# CL-KB-V1_2.net
KiCad netlist of a schematic drawn in Altium Designer
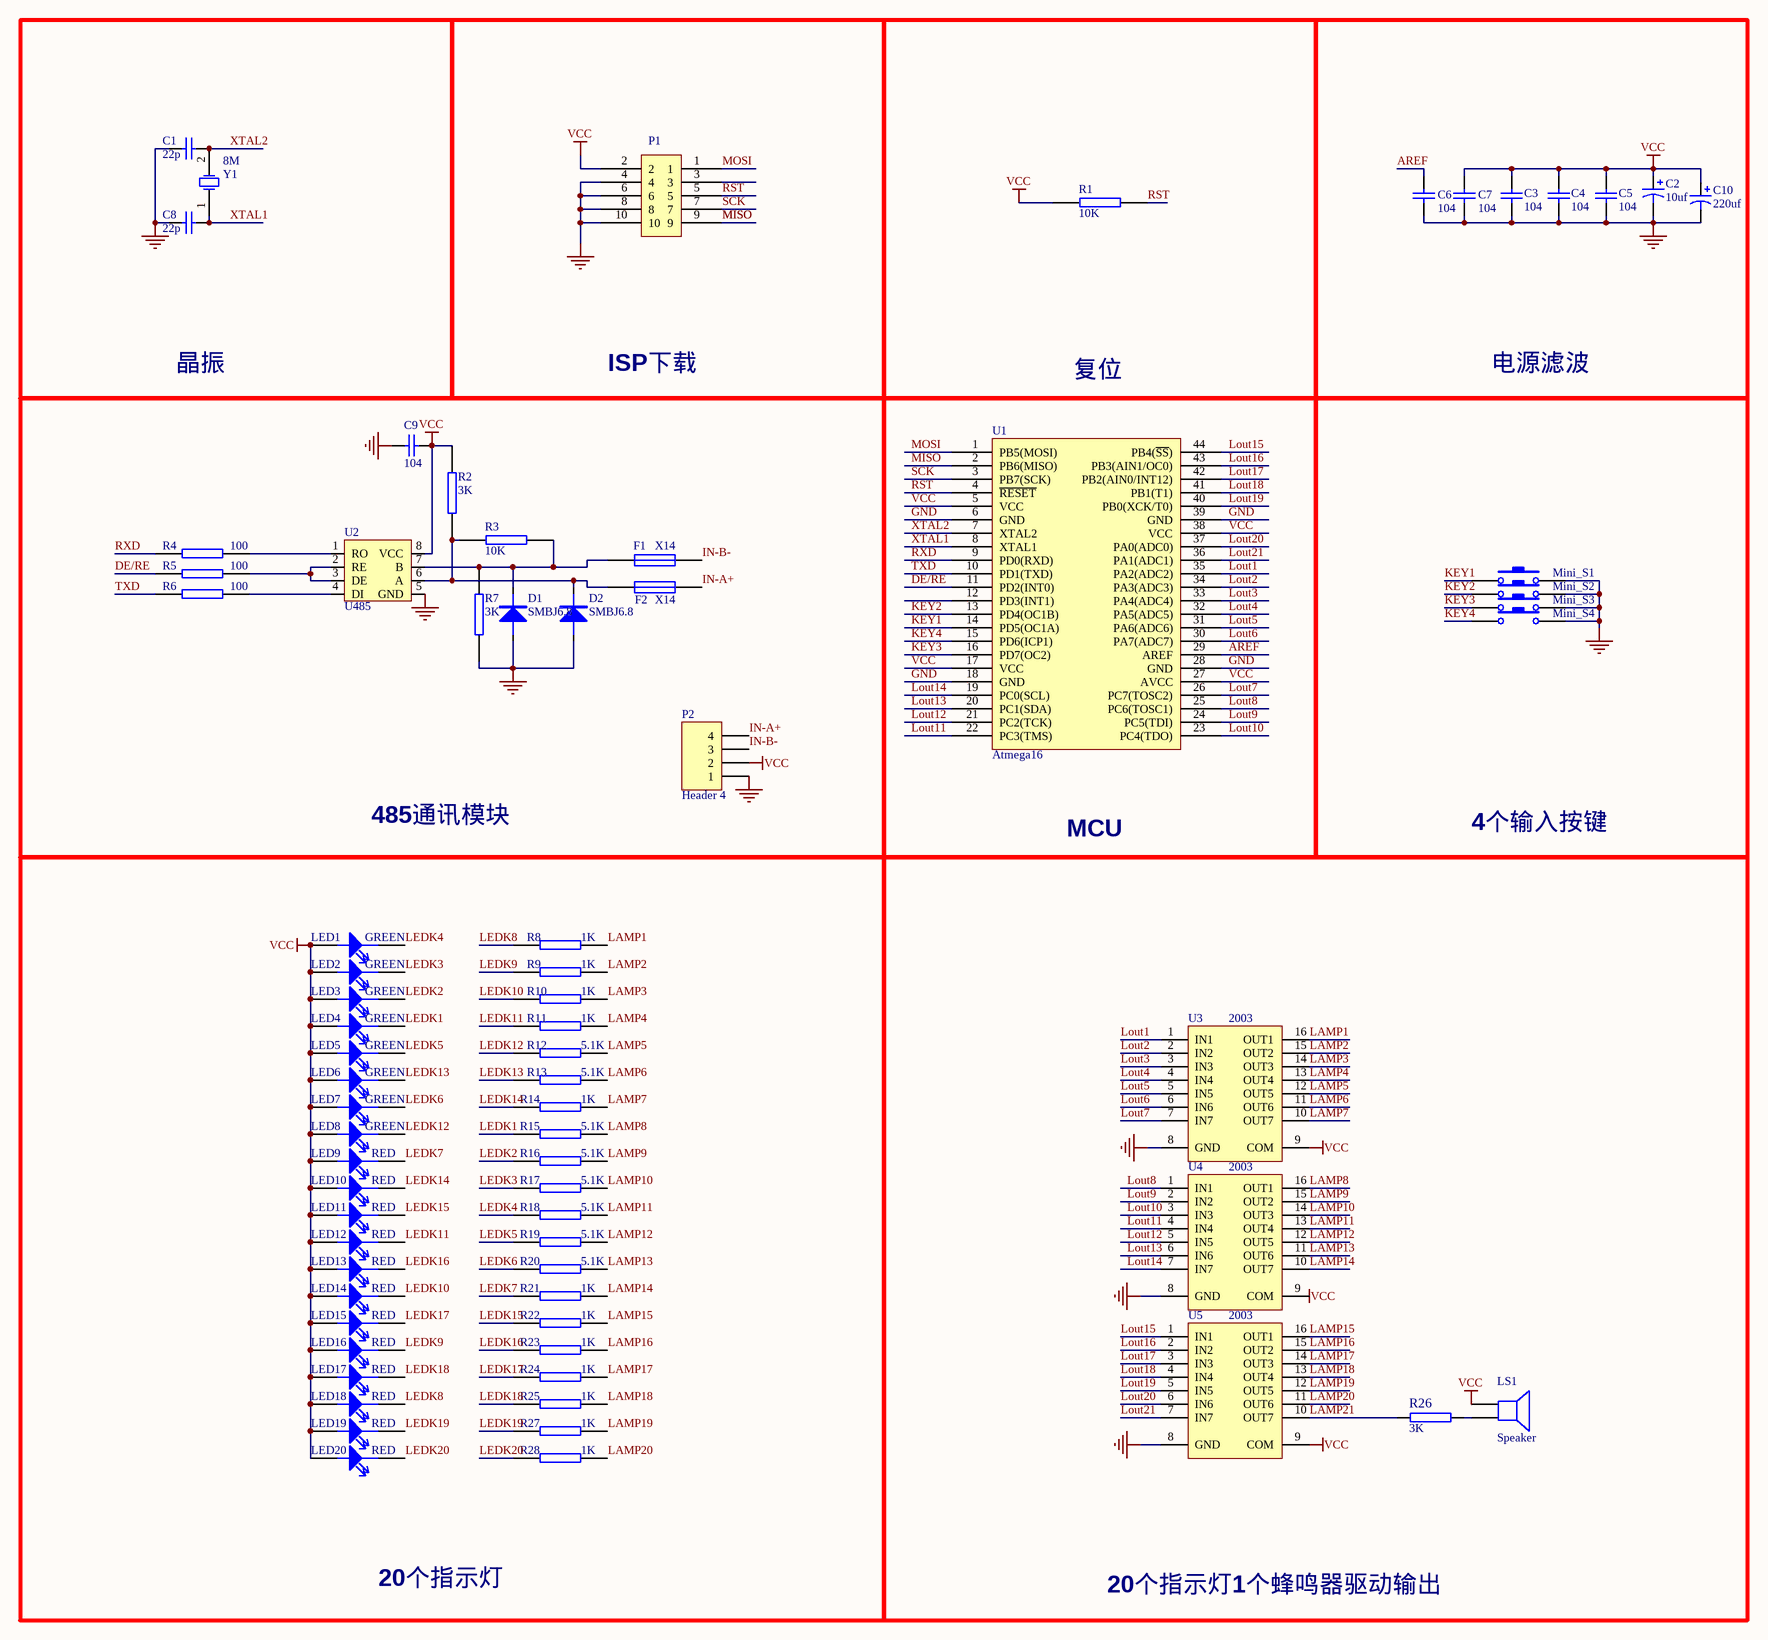
[diagram p0: CL-KB-V1.2.SchDoc]

(export (version "E")
  (design (tool "Eeschema 10.0.6"))
  (components
    (comp (ref "C1")
      (value "22p")
      (footprint "c0805c")
      (description "Capacitor")
      (fields (field (name "PUBLISHER") "Altium Limited"))
      (libsource (lib "*") (part "Cap"))
    )
    (comp (ref "C2")
      (value "10uf")
      (footprint "E6.5MM")
      (description "Polarized Capacitor (Radial)")
      (fields (field (name "PUBLISHER") "Altium Limited"))
      (libsource (lib "PCB_Project1") (part "Cap Pol1"))
    )
    (comp (ref "C3")
      (value "104")
      (footprint "c0805c")
      (description "Capacitor")
      (fields (field (name "PUBLISHER") "Altium Limited"))
      (libsource (lib "*") (part "Cap"))
    )
    (comp (ref "C4")
      (value "104")
      (footprint "c0805c")
      (description "Capacitor")
      (fields (field (name "PUBLISHER") "Altium Limited"))
      (libsource (lib "*") (part "Cap"))
    )
    (comp (ref "C5")
      (value "104")
      (footprint "c0805c")
      (description "Capacitor")
      (fields (field (name "PUBLISHER") "Altium Limited"))
      (libsource (lib "*") (part "Cap"))
    )
    (comp (ref "C6")
      (value "104")
      (footprint "c0805c")
      (description "Capacitor")
      (fields (field (name "PUBLISHER") "Altium Limited"))
      (libsource (lib "*") (part "Cap"))
    )
    (comp (ref "C7")
      (value "104")
      (footprint "c0805c")
      (description "Capacitor")
      (fields (field (name "PUBLISHER") "Altium Limited"))
      (libsource (lib "*") (part "Cap"))
    )
    (comp (ref "C8")
      (value "22p")
      (footprint "c0805c")
      (description "Capacitor")
      (fields (field (name "PUBLISHER") "Altium Limited"))
      (libsource (lib "*") (part "Cap"))
    )
    (comp (ref "C9")
      (value "104")
      (footprint "c0805c")
      (description "Capacitor")
      (fields (field (name "PUBLISHER") "Altium Limited"))
      (libsource (lib "*") (part "Cap"))
    )
    (comp (ref "C10")
      (value "220uf")
      (footprint "E6.5MM")
      (description "Polarized Capacitor (Radial)")
      (fields (field (name "PUBLISHER") "Altium Limited"))
      (libsource (lib "PCB_Project1") (part "Cap Pol1"))
    )
    (comp (ref "D1")
      (value "SMBJ6.8")
      (footprint "SMBJ_SMT")
      (description "Diode")
      (libsource (lib "*") (part "DIODE"))
    )
    (comp (ref "D2")
      (value "SMBJ6.8")
      (footprint "SMBJ_SMT")
      (description "Diode")
      (libsource (lib "*") (part "DIODE"))
    )
    (comp (ref "F1")
      (value "X14")
      (footprint "PPTC_SMT")
      (description "Fuse")
      (fields (field (name "PUBLISHER") "Altium Limited"))
      (libsource (lib "Miscellaneous Devices") (part "Fuse 1"))
    )
    (comp (ref "F2")
      (value "X14")
      (footprint "PPTC_SMT")
      (description "Fuse")
      (fields (field (name "PUBLISHER") "Altium Limited"))
      (libsource (lib "Miscellaneous Devices") (part "Fuse 1"))
    )
    (comp (ref "LED1")
      (value "GREEN")
      (footprint "PLED10*10")
      (description "Zener Diode")
      (libsource (lib "*") (part "LED"))
    )
    (comp (ref "LED2")
      (value "GREEN")
      (footprint "PLED10*10")
      (description "Zener Diode")
      (libsource (lib "*") (part "LED"))
    )
    (comp (ref "LED3")
      (value "GREEN")
      (footprint "PLED10*10")
      (description "Zener Diode")
      (libsource (lib "*") (part "LED"))
    )
    (comp (ref "LED4")
      (value "GREEN")
      (footprint "PLED10*10")
      (description "Zener Diode")
      (libsource (lib "*") (part "LED"))
    )
    (comp (ref "LED5")
      (value "GREEN")
      (footprint "PLED10*10")
      (description "Zener Diode")
      (libsource (lib "*") (part "LED"))
    )
    (comp (ref "LED6")
      (value "GREEN")
      (footprint "PLED10*10")
      (description "Zener Diode")
      (libsource (lib "*") (part "LED"))
    )
    (comp (ref "LED7")
      (value "GREEN")
      (footprint "PLED10*10")
      (description "Zener Diode")
      (libsource (lib "*") (part "LED"))
    )
    (comp (ref "LED8")
      (value "GREEN")
      (footprint "PLED10*10")
      (description "Zener Diode")
      (libsource (lib "*") (part "LED"))
    )
    (comp (ref "LED9")
      (value "RED")
      (footprint "PLED10*10")
      (description "Zener Diode")
      (libsource (lib "*") (part "LED"))
    )
    (comp (ref "LED10")
      (value "RED")
      (footprint "PLED10*10")
      (description "Zener Diode")
      (libsource (lib "*") (part "LED"))
    )
    (comp (ref "LED11")
      (value "RED")
      (footprint "PLED10*10")
      (description "Zener Diode")
      (libsource (lib "*") (part "LED"))
    )
    (comp (ref "LED12")
      (value "RED")
      (footprint "PLED10*10")
      (description "Zener Diode")
      (libsource (lib "*") (part "LED"))
    )
    (comp (ref "LED13")
      (value "RED")
      (footprint "PLED10*10")
      (description "Zener Diode")
      (libsource (lib "*") (part "LED"))
    )
    (comp (ref "LED14")
      (value "RED")
      (footprint "PLED10*10")
      (description "Zener Diode")
      (libsource (lib "*") (part "LED"))
    )
    (comp (ref "LED15")
      (value "RED")
      (footprint "PLED10*10")
      (description "Zener Diode")
      (libsource (lib "*") (part "LED"))
    )
    (comp (ref "LED16")
      (value "RED")
      (footprint "PLED10*10")
      (description "Zener Diode")
      (libsource (lib "*") (part "LED"))
    )
    (comp (ref "LED17")
      (value "RED")
      (footprint "PLED10*10")
      (description "Zener Diode")
      (libsource (lib "*") (part "LED"))
    )
    (comp (ref "LED18")
      (value "RED")
      (footprint "PLED10*10")
      (description "Zener Diode")
      (libsource (lib "*") (part "LED"))
    )
    (comp (ref "LED19")
      (value "RED")
      (footprint "PLED10*10")
      (description "Zener Diode")
      (libsource (lib "*") (part "LED"))
    )
    (comp (ref "LED20")
      (value "RED")
      (footprint "PLED10*10")
      (description "Zener Diode")
      (libsource (lib "*") (part "LED"))
    )
    (comp (ref "LS1")
      (value "Speaker")
      (footprint "SPK")
      (description "Loudspeaker")
      (fields (field (name "PUBLISHER") "Altium Limited"))
      (libsource (lib "Miscellaneous Devices") (part "Speaker"))
    )
    (comp (ref "Mini_S1")
      (value "~")
      (footprint "KEYL")
      (description "Switch")
      (fields (field (name "PUBLISHER") "Altium Limited"))
      (libsource (lib "Miscellaneous Devices") (part "SW-PB"))
    )
    (comp (ref "Mini_S2")
      (value "~")
      (footprint "KEYL")
      (description "Switch")
      (fields (field (name "PUBLISHER") "Altium Limited"))
      (libsource (lib "Miscellaneous Devices") (part "SW-PB"))
    )
    (comp (ref "Mini_S3")
      (value "~")
      (footprint "KEYL")
      (description "Switch")
      (fields (field (name "PUBLISHER") "Altium Limited"))
      (libsource (lib "Miscellaneous Devices") (part "SW-PB"))
    )
    (comp (ref "Mini_S4")
      (value "~")
      (footprint "KEYL")
      (description "Switch")
      (fields (field (name "PUBLISHER") "Altium Limited"))
      (libsource (lib "Miscellaneous Devices") (part "SW-PB"))
    )
    (comp (ref "P1") (value "CON10") (footprint "ISP") (libsource (lib "能迪SCH库") (part "SPI10")))
    (comp (ref "P2")
      (value "Header 4")
      (footprint "C3-4L")
      (description "Header, 4-Pin")
      (fields (field (name "PUBLISHER") "Altium Limited"))
      (libsource (lib "Miscellaneous Connectors") (part "Header 4"))
    )
    (comp (ref "R1") (value "10K") (footprint "0805C") (libsource (lib "") (part "RES2_1")))
    (comp (ref "R2") (value "3K") (footprint "0805C") (libsource (lib "") (part "RES2_1")))
    (comp (ref "R3") (value "10K") (footprint "0805C") (libsource (lib "") (part "RES2_1")))
    (comp (ref "R4") (value "100") (footprint "0805C") (libsource (lib "*") (part "RES2")))
    (comp (ref "R5") (value "100") (footprint "0805C") (libsource (lib "*") (part "RES2")))
    (comp (ref "R6") (value "100") (footprint "0805C") (libsource (lib "*") (part "RES2")))
    (comp (ref "R7") (value "3K") (footprint "0805C") (libsource (lib "") (part "RES2_1")))
    (comp (ref "R8") (value "1K") (footprint "0805C") (libsource (lib "") (part "RES2_1")))
    (comp (ref "R9") (value "1K") (footprint "0805C") (libsource (lib "") (part "RES2_1")))
    (comp (ref "R10") (value "1K") (footprint "0805C") (libsource (lib "") (part "RES2_1")))
    (comp (ref "R11") (value "1K") (footprint "0805C") (libsource (lib "") (part "RES2_1")))
    (comp (ref "R12") (value "5.1K") (footprint "0805C") (libsource (lib "") (part "RES2_1")))
    (comp (ref "R13") (value "5.1K") (footprint "0805C") (libsource (lib "") (part "RES2_1")))
    (comp (ref "R14") (value "1K") (footprint "0805C") (libsource (lib "") (part "RES2_1")))
    (comp (ref "R15") (value "5.1K") (footprint "0805C") (libsource (lib "") (part "RES2_1")))
    (comp (ref "R16") (value "5.1K") (footprint "0805C") (libsource (lib "") (part "RES2_1")))
    (comp (ref "R17") (value "5.1K") (footprint "0805C") (libsource (lib "") (part "RES2_1")))
    (comp (ref "R18") (value "5.1K") (footprint "0805C") (libsource (lib "") (part "RES2_1")))
    (comp (ref "R19") (value "5.1K") (footprint "0805C") (libsource (lib "") (part "RES2_1")))
    (comp (ref "R20") (value "5.1K") (footprint "0805C") (libsource (lib "") (part "RES2_1")))
    (comp (ref "R21") (value "1K") (footprint "0805C") (libsource (lib "") (part "RES2_1")))
    (comp (ref "R22") (value "1K") (footprint "0805C") (libsource (lib "") (part "RES2_1")))
    (comp (ref "R23") (value "1K") (footprint "0805C") (libsource (lib "") (part "RES2_1")))
    (comp (ref "R24") (value "1K") (footprint "0805C") (libsource (lib "") (part "RES2_1")))
    (comp (ref "R25") (value "1K") (footprint "0805C") (libsource (lib "") (part "RES2_1")))
    (comp (ref "R26") (value "3K") (footprint "0805C") (libsource (lib "") (part "RES2_2")))
    (comp (ref "R27") (value "1K") (footprint "0805C") (libsource (lib "") (part "RES2_1")))
    (comp (ref "R28") (value "1K") (footprint "0805C") (libsource (lib "") (part "RES2_1")))
    (comp (ref "U1")
      (value "Atmega16")
      (footprint "QFP44")
      (libsource (lib "CL_FS_A(V1.0)") (part "Atmega16"))
    )
    (comp (ref "U2") (value "U485") (footprint "SOP8") (libsource (lib "POL485") (part "U485")))
    (comp (ref "U3")
      (value "2003")
      (footprint "SO_16")
      (description "High-Voltage, High-Current Darlington Array")
      (fields (field (name "PUBLISHER") "*"))
      (libsource (lib "*") (part "ULN2003A"))
    )
    (comp (ref "U4")
      (value "2003")
      (footprint "SO_16")
      (description "High-Voltage, High-Current Darlington Array")
      (fields (field (name "PUBLISHER") "*"))
      (libsource (lib "*") (part "ULN2003A"))
    )
    (comp (ref "U5")
      (value "2003")
      (footprint "SO_16")
      (description "High-Voltage, High-Current Darlington Array")
      (fields (field (name "PUBLISHER") "*"))
      (libsource (lib "*") (part "ULN2003A"))
    )
    (comp (ref "Y1")
      (value "8M")
      (footprint "XTP2")
      (description "Crystal Oscillator")
      (fields (field (name "PUBLISHER") "Altium Limited"))
      (libsource (lib "*") (part "XTAL"))
    )
  )
  (nets
    (net (code "1") (name "/AREF") (class "Default")
      (node (ref "C6") (pin "2") (pinfunction "2_2") (pintype "passive"))
      (node (ref "U1") (pin "29") (pinfunction "AREF_29") (pintype "passive"))
    )
    (net (code "2") (name "/DE{slash}RE") (class "Default")
      (node (ref "R5") (pin "2") (pinfunction "2_2") (pintype "passive"))
      (node (ref "U1") (pin "11") (pinfunction "PD2(INT0)_11") (pintype "passive"))
    )
    (net (code "3") (name "/IN-A+") (class "Default")
      (node (ref "F2") (pin "1") (pinfunction "1_1") (pintype "passive"))
      (node (ref "P2") (pin "4") (pinfunction "4_4") (pintype "passive"))
    )
    (net (code "4") (name "/IN-B-") (class "Default")
      (node (ref "F1") (pin "1") (pinfunction "1_1") (pintype "passive"))
      (node (ref "P2") (pin "3") (pinfunction "3_3") (pintype "passive"))
    )
    (net (code "5") (name "/KEY1") (class "Default")
      (node (ref "Mini_S1") (pin "1") (pinfunction "1_1") (pintype "passive"))
      (node (ref "U1") (pin "14") (pinfunction "PD5(OC1A)_14") (pintype "passive"))
    )
    (net (code "6") (name "/KEY2") (class "Default")
      (node (ref "Mini_S2") (pin "1") (pinfunction "1_1") (pintype "passive"))
      (node (ref "U1") (pin "13") (pinfunction "PD4(OC1B)_13") (pintype "passive"))
    )
    (net (code "7") (name "/KEY3") (class "Default")
      (node (ref "Mini_S3") (pin "1") (pinfunction "1_1") (pintype "passive"))
      (node (ref "U1") (pin "16") (pinfunction "PD7(OC2)_16") (pintype "passive"))
    )
    (net (code "8") (name "/KEY4") (class "Default")
      (node (ref "Mini_S4") (pin "1") (pinfunction "1_1") (pintype "passive"))
      (node (ref "U1") (pin "15") (pinfunction "PD6(ICP1)_15") (pintype "passive"))
    )
    (net (code "9") (name "/LAMP1") (class "Default")
      (node (ref "R8") (pin "2") (pinfunction "2_2") (pintype "passive"))
      (node (ref "U3") (pin "16") (pinfunction "OUT1_16") (pintype "open_collector"))
    )
    (net (code "10") (name "/LAMP2") (class "Default")
      (node (ref "R9") (pin "2") (pinfunction "2_2") (pintype "passive"))
      (node (ref "U3") (pin "15") (pinfunction "OUT2_15") (pintype "open_collector"))
    )
    (net (code "11") (name "/LAMP3") (class "Default")
      (node (ref "R10") (pin "2") (pinfunction "2_2") (pintype "passive"))
      (node (ref "U3") (pin "14") (pinfunction "OUT3_14") (pintype "open_collector"))
    )
    (net (code "12") (name "/LAMP4") (class "Default")
      (node (ref "R11") (pin "2") (pinfunction "2_2") (pintype "passive"))
      (node (ref "U3") (pin "13") (pinfunction "OUT4_13") (pintype "open_collector"))
    )
    (net (code "13") (name "/LAMP5") (class "Default")
      (node (ref "R12") (pin "2") (pinfunction "2_2") (pintype "passive"))
      (node (ref "U3") (pin "12") (pinfunction "OUT5_12") (pintype "open_collector"))
    )
    (net (code "14") (name "/LAMP6") (class "Default")
      (node (ref "R13") (pin "2") (pinfunction "2_2") (pintype "passive"))
      (node (ref "U3") (pin "11") (pinfunction "OUT6_11") (pintype "open_collector"))
    )
    (net (code "15") (name "/LAMP7") (class "Default")
      (node (ref "R14") (pin "2") (pinfunction "2_2") (pintype "passive"))
      (node (ref "U3") (pin "10") (pinfunction "OUT7_10") (pintype "open_collector"))
    )
    (net (code "16") (name "/LAMP8") (class "Default")
      (node (ref "R15") (pin "2") (pinfunction "2_2") (pintype "passive"))
      (node (ref "U4") (pin "16") (pinfunction "OUT1_16") (pintype "open_collector"))
    )
    (net (code "17") (name "/LAMP9") (class "Default")
      (node (ref "R16") (pin "2") (pinfunction "2_2") (pintype "passive"))
      (node (ref "U4") (pin "15") (pinfunction "OUT2_15") (pintype "open_collector"))
    )
    (net (code "18") (name "/LAMP10") (class "Default")
      (node (ref "R17") (pin "2") (pinfunction "2_2") (pintype "passive"))
      (node (ref "U4") (pin "14") (pinfunction "OUT3_14") (pintype "open_collector"))
    )
    (net (code "19") (name "/LAMP11") (class "Default")
      (node (ref "R18") (pin "2") (pinfunction "2_2") (pintype "passive"))
      (node (ref "U4") (pin "13") (pinfunction "OUT4_13") (pintype "open_collector"))
    )
    (net (code "20") (name "/LAMP12") (class "Default")
      (node (ref "R19") (pin "2") (pinfunction "2_2") (pintype "passive"))
      (node (ref "U4") (pin "12") (pinfunction "OUT5_12") (pintype "open_collector"))
    )
    (net (code "21") (name "/LAMP13") (class "Default")
      (node (ref "R20") (pin "2") (pinfunction "2_2") (pintype "passive"))
      (node (ref "U4") (pin "11") (pinfunction "OUT6_11") (pintype "open_collector"))
    )
    (net (code "22") (name "/LAMP14") (class "Default")
      (node (ref "R21") (pin "2") (pinfunction "2_2") (pintype "passive"))
      (node (ref "U4") (pin "10") (pinfunction "OUT7_10") (pintype "open_collector"))
    )
    (net (code "23") (name "/LAMP15") (class "Default")
      (node (ref "R22") (pin "2") (pinfunction "2_2") (pintype "passive"))
      (node (ref "U5") (pin "16") (pinfunction "OUT1_16") (pintype "open_collector"))
    )
    (net (code "24") (name "/LAMP16") (class "Default")
      (node (ref "R23") (pin "2") (pinfunction "2_2") (pintype "passive"))
      (node (ref "U5") (pin "15") (pinfunction "OUT2_15") (pintype "open_collector"))
    )
    (net (code "25") (name "/LAMP17") (class "Default")
      (node (ref "R24") (pin "2") (pinfunction "2_2") (pintype "passive"))
      (node (ref "U5") (pin "14") (pinfunction "OUT3_14") (pintype "open_collector"))
    )
    (net (code "26") (name "/LAMP18") (class "Default")
      (node (ref "R25") (pin "2") (pinfunction "2_2") (pintype "passive"))
      (node (ref "U5") (pin "13") (pinfunction "OUT4_13") (pintype "open_collector"))
    )
    (net (code "27") (name "/LAMP19") (class "Default")
      (node (ref "R27") (pin "2") (pinfunction "2_2") (pintype "passive"))
      (node (ref "U5") (pin "12") (pinfunction "OUT5_12") (pintype "open_collector"))
    )
    (net (code "28") (name "/LAMP20") (class "Default")
      (node (ref "R28") (pin "2") (pinfunction "2_2") (pintype "passive"))
      (node (ref "U5") (pin "11") (pinfunction "OUT6_11") (pintype "open_collector"))
    )
    (net (code "29") (name "/LAMP21") (class "Default")
      (node (ref "R26") (pin "1") (pintype "passive"))
      (node (ref "U5") (pin "10") (pinfunction "OUT7_10") (pintype "open_collector"))
    )
    (net (code "30") (name "/LEDK1") (class "Default")
      (node (ref "LED4") (pin "K") (pinfunction "K_K") (pintype "passive"))
      (node (ref "R15") (pin "1") (pinfunction "1_1") (pintype "passive"))
    )
    (net (code "31") (name "/LEDK2") (class "Default")
      (node (ref "LED3") (pin "K") (pinfunction "K_K") (pintype "passive"))
      (node (ref "R16") (pin "1") (pinfunction "1_1") (pintype "passive"))
    )
    (net (code "32") (name "/LEDK3") (class "Default")
      (node (ref "LED2") (pin "K") (pinfunction "K_K") (pintype "passive"))
      (node (ref "R17") (pin "1") (pinfunction "1_1") (pintype "passive"))
    )
    (net (code "33") (name "/LEDK4") (class "Default")
      (node (ref "LED1") (pin "K") (pinfunction "K_K") (pintype "passive"))
      (node (ref "R18") (pin "1") (pinfunction "1_1") (pintype "passive"))
    )
    (net (code "34") (name "/LEDK5") (class "Default")
      (node (ref "LED5") (pin "K") (pinfunction "K_K") (pintype "passive"))
      (node (ref "R19") (pin "1") (pinfunction "1_1") (pintype "passive"))
    )
    (net (code "35") (name "/LEDK6") (class "Default")
      (node (ref "LED7") (pin "K") (pinfunction "K_K") (pintype "passive"))
      (node (ref "R20") (pin "1") (pinfunction "1_1") (pintype "passive"))
    )
    (net (code "36") (name "/LEDK7") (class "Default")
      (node (ref "LED9") (pin "K") (pinfunction "K_K") (pintype "passive"))
      (node (ref "R21") (pin "1") (pinfunction "1_1") (pintype "passive"))
    )
    (net (code "37") (name "/LEDK8") (class "Default")
      (node (ref "LED18") (pin "K") (pinfunction "K_K") (pintype "passive"))
      (node (ref "R8") (pin "1") (pinfunction "1_1") (pintype "passive"))
    )
    (net (code "38") (name "/LEDK9") (class "Default")
      (node (ref "LED16") (pin "K") (pinfunction "K_K") (pintype "passive"))
      (node (ref "R9") (pin "1") (pinfunction "1_1") (pintype "passive"))
    )
    (net (code "39") (name "/LEDK10") (class "Default")
      (node (ref "LED14") (pin "K") (pinfunction "K_K") (pintype "passive"))
      (node (ref "R10") (pin "1") (pinfunction "1_1") (pintype "passive"))
    )
    (net (code "40") (name "/LEDK11") (class "Default")
      (node (ref "LED12") (pin "K") (pinfunction "K_K") (pintype "passive"))
      (node (ref "R11") (pin "1") (pinfunction "1_1") (pintype "passive"))
    )
    (net (code "41") (name "/LEDK12") (class "Default")
      (node (ref "LED8") (pin "K") (pinfunction "K_K") (pintype "passive"))
      (node (ref "R12") (pin "1") (pinfunction "1_1") (pintype "passive"))
    )
    (net (code "42") (name "/LEDK13") (class "Default")
      (node (ref "LED6") (pin "K") (pinfunction "K_K") (pintype "passive"))
      (node (ref "R13") (pin "1") (pinfunction "1_1") (pintype "passive"))
    )
    (net (code "43") (name "/LEDK14") (class "Default")
      (node (ref "LED10") (pin "K") (pinfunction "K_K") (pintype "passive"))
      (node (ref "R14") (pin "1") (pinfunction "1_1") (pintype "passive"))
    )
    (net (code "44") (name "/LEDK15") (class "Default")
      (node (ref "LED11") (pin "K") (pinfunction "K_K") (pintype "passive"))
      (node (ref "R22") (pin "1") (pinfunction "1_1") (pintype "passive"))
    )
    (net (code "45") (name "/LEDK16") (class "Default")
      (node (ref "LED13") (pin "K") (pinfunction "K_K") (pintype "passive"))
      (node (ref "R23") (pin "1") (pinfunction "1_1") (pintype "passive"))
    )
    (net (code "46") (name "/LEDK17") (class "Default")
      (node (ref "LED15") (pin "K") (pinfunction "K_K") (pintype "passive"))
      (node (ref "R24") (pin "1") (pinfunction "1_1") (pintype "passive"))
    )
    (net (code "47") (name "/LEDK18") (class "Default")
      (node (ref "LED17") (pin "K") (pinfunction "K_K") (pintype "passive"))
      (node (ref "R25") (pin "1") (pinfunction "1_1") (pintype "passive"))
    )
    (net (code "48") (name "/LEDK19") (class "Default")
      (node (ref "LED19") (pin "K") (pinfunction "K_K") (pintype "passive"))
      (node (ref "R27") (pin "1") (pinfunction "1_1") (pintype "passive"))
    )
    (net (code "49") (name "/LEDK20") (class "Default")
      (node (ref "LED20") (pin "K") (pinfunction "K_K") (pintype "passive"))
      (node (ref "R28") (pin "1") (pinfunction "1_1") (pintype "passive"))
    )
    (net (code "50") (name "/Lout1") (class "Default")
      (node (ref "U1") (pin "35") (pinfunction "PA2(ADC2)_35") (pintype "passive"))
      (node (ref "U3") (pin "1") (pinfunction "IN1_1") (pintype "passive"))
    )
    (net (code "51") (name "/Lout2") (class "Default")
      (node (ref "U1") (pin "34") (pinfunction "PA3(ADC3)_34") (pintype "passive"))
      (node (ref "U3") (pin "2") (pinfunction "IN2_2") (pintype "passive"))
    )
    (net (code "52") (name "/Lout3") (class "Default")
      (node (ref "U1") (pin "33") (pinfunction "PA4(ADC4)_33") (pintype "passive"))
      (node (ref "U3") (pin "3") (pinfunction "IN3_3") (pintype "passive"))
    )
    (net (code "53") (name "/Lout4") (class "Default")
      (node (ref "U1") (pin "32") (pinfunction "PA5(ADC5)_32") (pintype "passive"))
      (node (ref "U3") (pin "4") (pinfunction "IN4_4") (pintype "passive"))
    )
    (net (code "54") (name "/Lout5") (class "Default")
      (node (ref "U1") (pin "31") (pinfunction "PA6(ADC6)_31") (pintype "passive"))
      (node (ref "U3") (pin "5") (pinfunction "IN5_5") (pintype "passive"))
    )
    (net (code "55") (name "/Lout6") (class "Default")
      (node (ref "U1") (pin "30") (pinfunction "PA7(ADC7)_30") (pintype "passive"))
      (node (ref "U3") (pin "6") (pinfunction "IN6_6") (pintype "passive"))
    )
    (net (code "56") (name "/Lout7") (class "Default")
      (node (ref "U1") (pin "26") (pinfunction "PC7(TOSC2)_26") (pintype "passive"))
      (node (ref "U3") (pin "7") (pinfunction "IN7_7") (pintype "passive"))
    )
    (net (code "57") (name "/Lout8") (class "Default")
      (node (ref "U1") (pin "25") (pinfunction "PC6(TOSC1)_25") (pintype "passive"))
      (node (ref "U4") (pin "1") (pinfunction "IN1_1") (pintype "passive"))
    )
    (net (code "58") (name "/Lout9") (class "Default")
      (node (ref "U1") (pin "24") (pinfunction "PC5(TDI)_24") (pintype "passive"))
      (node (ref "U4") (pin "2") (pinfunction "IN2_2") (pintype "passive"))
    )
    (net (code "59") (name "/Lout10") (class "Default")
      (node (ref "U1") (pin "23") (pinfunction "PC4(TDO)_23") (pintype "passive"))
      (node (ref "U4") (pin "3") (pinfunction "IN3_3") (pintype "passive"))
    )
    (net (code "60") (name "/Lout11") (class "Default")
      (node (ref "U1") (pin "22") (pinfunction "PC3(TMS)_22") (pintype "passive"))
      (node (ref "U4") (pin "4") (pinfunction "IN4_4") (pintype "passive"))
    )
    (net (code "61") (name "/Lout12") (class "Default")
      (node (ref "U1") (pin "21") (pinfunction "PC2(TCK)_21") (pintype "passive"))
      (node (ref "U4") (pin "5") (pinfunction "IN5_5") (pintype "passive"))
    )
    (net (code "62") (name "/Lout13") (class "Default")
      (node (ref "U1") (pin "20") (pinfunction "PC1(SDA)_20") (pintype "passive"))
      (node (ref "U4") (pin "6") (pinfunction "IN6_6") (pintype "passive"))
    )
    (net (code "63") (name "/Lout14") (class "Default")
      (node (ref "U1") (pin "19") (pinfunction "PC0(SCL)_19") (pintype "passive"))
      (node (ref "U4") (pin "7") (pinfunction "IN7_7") (pintype "passive"))
    )
    (net (code "64") (name "/Lout15") (class "Default")
      (node (ref "U1") (pin "44") (pinfunction "PB4(~{SS})_44") (pintype "passive"))
      (node (ref "U5") (pin "1") (pinfunction "IN1_1") (pintype "passive"))
    )
    (net (code "65") (name "/Lout16") (class "Default")
      (node (ref "U1") (pin "43") (pinfunction "PB3(AIN1/OC0)_43") (pintype "passive"))
      (node (ref "U5") (pin "2") (pinfunction "IN2_2") (pintype "passive"))
    )
    (net (code "66") (name "/Lout17") (class "Default")
      (node (ref "U1") (pin "42") (pinfunction "PB2(AIN0/INT12)_42") (pintype "passive"))
      (node (ref "U5") (pin "3") (pinfunction "IN3_3") (pintype "passive"))
    )
    (net (code "67") (name "/Lout18") (class "Default")
      (node (ref "U1") (pin "41") (pinfunction "PB1(T1)_41") (pintype "passive"))
      (node (ref "U5") (pin "4") (pinfunction "IN4_4") (pintype "passive"))
    )
    (net (code "68") (name "/Lout19") (class "Default")
      (node (ref "U1") (pin "40") (pinfunction "PB0(XCK/T0)_40") (pintype "passive"))
      (node (ref "U5") (pin "5") (pinfunction "IN5_5") (pintype "passive"))
    )
    (net (code "69") (name "/Lout20") (class "Default")
      (node (ref "U1") (pin "37") (pinfunction "PA0(ADC0)_37") (pintype "passive"))
      (node (ref "U5") (pin "6") (pinfunction "IN6_6") (pintype "passive"))
    )
    (net (code "70") (name "/Lout21") (class "Default")
      (node (ref "U1") (pin "36") (pinfunction "PA1(ADC1)_36") (pintype "passive"))
      (node (ref "U5") (pin "7") (pinfunction "IN7_7") (pintype "passive"))
    )
    (net (code "71") (name "/MISO") (class "Default")
      (node (ref "P1") (pin "9") (pinfunction "9_9") (pintype "passive"))
      (node (ref "U1") (pin "2") (pinfunction "PB6(MISO)_2") (pintype "passive"))
    )
    (net (code "72") (name "/MOSI") (class "Default")
      (node (ref "P1") (pin "1") (pinfunction "1_1") (pintype "passive"))
      (node (ref "U1") (pin "1") (pinfunction "PB5(MOSI)_1") (pintype "passive"))
    )
    (net (code "73") (name "/RST") (class "Default")
      (node (ref "P1") (pin "5") (pinfunction "5_5") (pintype "passive"))
      (node (ref "R1") (pin "1") (pinfunction "1_1") (pintype "passive"))
      (node (ref "U1") (pin "4") (pinfunction "~{RESET}_4") (pintype "passive"))
    )
    (net (code "74") (name "/RXD") (class "Default")
      (node (ref "R4") (pin "2") (pinfunction "2_2") (pintype "passive"))
      (node (ref "U1") (pin "9") (pinfunction "PD0(RXD)_9") (pintype "passive"))
    )
    (net (code "75") (name "/SCK") (class "Default")
      (node (ref "P1") (pin "7") (pinfunction "7_7") (pintype "passive"))
      (node (ref "U1") (pin "3") (pinfunction "PB7(SCK)_3") (pintype "passive"))
    )
    (net (code "76") (name "/TXD") (class "Default")
      (node (ref "R6") (pin "2") (pinfunction "2_2") (pintype "passive"))
      (node (ref "U1") (pin "10") (pinfunction "PD1(TXD)_10") (pintype "passive"))
    )
    (net (code "77") (name "/XTAL1") (class "Default")
      (node (ref "C8") (pin "1") (pinfunction "1_1") (pintype "passive"))
      (node (ref "U1") (pin "8") (pinfunction "XTAL1_8") (pintype "passive"))
      (node (ref "Y1") (pin "1") (pinfunction "OSC1_1") (pintype "passive"))
    )
    (net (code "78") (name "/XTAL2") (class "Default")
      (node (ref "C1") (pin "1") (pinfunction "1_1") (pintype "passive"))
      (node (ref "U1") (pin "7") (pinfunction "XTAL2_7") (pintype "passive"))
      (node (ref "Y1") (pin "2") (pinfunction "OSC2_2") (pintype "passive"))
    )
    (net (code "79") (name "GND") (class "Default")
      (node (ref "C1") (pin "2") (pinfunction "2_2") (pintype "passive"))
      (node (ref "C10") (pin "2") (pinfunction "2_2") (pintype "passive"))
      (node (ref "C2") (pin "2") (pinfunction "2_2") (pintype "passive"))
      (node (ref "C3") (pin "1") (pinfunction "1_1") (pintype "passive"))
      (node (ref "C4") (pin "1") (pinfunction "1_1") (pintype "passive"))
      (node (ref "C5") (pin "2") (pinfunction "2_2") (pintype "passive"))
      (node (ref "C6") (pin "1") (pinfunction "1_1") (pintype "passive"))
      (node (ref "C7") (pin "1") (pinfunction "1_1") (pintype "passive"))
      (node (ref "C8") (pin "2") (pinfunction "2_2") (pintype "passive"))
      (node (ref "C9") (pin "2") (pinfunction "2_2") (pintype "passive"))
      (node (ref "D1") (pin "A") (pinfunction "A_A") (pintype "passive"))
      (node (ref "D2") (pin "A") (pinfunction "A_A") (pintype "passive"))
      (node (ref "Mini_S1") (pin "2") (pinfunction "2_2") (pintype "passive"))
      (node (ref "Mini_S2") (pin "2") (pinfunction "2_2") (pintype "passive"))
      (node (ref "Mini_S3") (pin "2") (pinfunction "2_2") (pintype "passive"))
      (node (ref "Mini_S4") (pin "2") (pinfunction "2_2") (pintype "passive"))
      (node (ref "P1") (pin "10") (pinfunction "10_10") (pintype "passive"))
      (node (ref "P1") (pin "4") (pinfunction "4_4") (pintype "passive"))
      (node (ref "P1") (pin "6") (pinfunction "6_6") (pintype "passive"))
      (node (ref "P1") (pin "8") (pinfunction "8_8") (pintype "passive"))
      (node (ref "P2") (pin "1") (pinfunction "1_1") (pintype "passive"))
      (node (ref "R7") (pin "1") (pinfunction "1_1") (pintype "passive"))
      (node (ref "U1") (pin "18") (pinfunction "GND_18") (pintype "passive"))
      (node (ref "U1") (pin "28") (pinfunction "GND_28") (pintype "passive"))
      (node (ref "U1") (pin "39") (pinfunction "GND_39") (pintype "passive"))
      (node (ref "U1") (pin "6") (pinfunction "GND_6") (pintype "passive"))
      (node (ref "U2") (pin "5") (pinfunction "GND_5") (pintype "passive"))
      (node (ref "U3") (pin "8") (pinfunction "GND_8") (pintype "power_in"))
      (node (ref "U4") (pin "8") (pinfunction "GND_8") (pintype "power_in"))
      (node (ref "U5") (pin "8") (pinfunction "GND_8") (pintype "power_in"))
    )
    (net (code "80") (name "Net-(LS1-Pad2)") (class "Default")
      (node (ref "LS1") (pin "2") (pinfunction "2_2") (pintype "passive"))
      (node (ref "R26") (pin "2") (pintype "passive"))
    )
    (net (code "81") (name "Net-(U2-A)") (class "Default")
      (node (ref "D2") (pin "K") (pinfunction "K_K") (pintype "passive"))
      (node (ref "F2") (pin "2") (pinfunction "2_2") (pintype "passive"))
      (node (ref "R2") (pin "2") (pinfunction "2_2") (pintype "passive"))
      (node (ref "R3") (pin "2") (pinfunction "2_2") (pintype "passive"))
      (node (ref "U2") (pin "6") (pinfunction "A_6") (pintype "passive"))
    )
    (net (code "82") (name "Net-(U2-B)") (class "Default")
      (node (ref "D1") (pin "K") (pinfunction "K_K") (pintype "passive"))
      (node (ref "F1") (pin "2") (pinfunction "2_2") (pintype "passive"))
      (node (ref "R3") (pin "1") (pinfunction "1_1") (pintype "passive"))
      (node (ref "R7") (pin "2") (pinfunction "2_2") (pintype "passive"))
      (node (ref "U2") (pin "7") (pinfunction "B_7") (pintype "passive"))
    )
    (net (code "83") (name "Net-(U2-DE)") (class "Default")
      (node (ref "R5") (pin "1") (pinfunction "1_1") (pintype "passive"))
      (node (ref "U2") (pin "2") (pinfunction "RE_2") (pintype "passive"))
      (node (ref "U2") (pin "3") (pinfunction "DE_3") (pintype "passive"))
    )
    (net (code "84") (name "Net-(U2-DI)") (class "Default")
      (node (ref "R6") (pin "1") (pinfunction "1_1") (pintype "passive"))
      (node (ref "U2") (pin "4") (pinfunction "DI_4") (pintype "passive"))
    )
    (net (code "85") (name "Net-(U2-RO)") (class "Default")
      (node (ref "R4") (pin "1") (pinfunction "1_1") (pintype "passive"))
      (node (ref "U2") (pin "1") (pinfunction "RO_1") (pintype "passive"))
    )
    (net (code "86") (name "VCC") (class "Default")
      (node (ref "C10") (pin "1") (pinfunction "1_1") (pintype "passive"))
      (node (ref "C2") (pin "1") (pinfunction "1_1") (pintype "passive"))
      (node (ref "C3") (pin "2") (pinfunction "2_2") (pintype "passive"))
      (node (ref "C4") (pin "2") (pinfunction "2_2") (pintype "passive"))
      (node (ref "C5") (pin "1") (pinfunction "1_1") (pintype "passive"))
      (node (ref "C7") (pin "2") (pinfunction "2_2") (pintype "passive"))
      (node (ref "C9") (pin "1") (pinfunction "1_1") (pintype "passive"))
      (node (ref "LED1") (pin "A") (pinfunction "A_A") (pintype "passive"))
      (node (ref "LED10") (pin "A") (pinfunction "A_A") (pintype "passive"))
      (node (ref "LED11") (pin "A") (pinfunction "A_A") (pintype "passive"))
      (node (ref "LED12") (pin "A") (pinfunction "A_A") (pintype "passive"))
      (node (ref "LED13") (pin "A") (pinfunction "A_A") (pintype "passive"))
      (node (ref "LED14") (pin "A") (pinfunction "A_A") (pintype "passive"))
      (node (ref "LED15") (pin "A") (pinfunction "A_A") (pintype "passive"))
      (node (ref "LED16") (pin "A") (pinfunction "A_A") (pintype "passive"))
      (node (ref "LED17") (pin "A") (pinfunction "A_A") (pintype "passive"))
      (node (ref "LED18") (pin "A") (pinfunction "A_A") (pintype "passive"))
      (node (ref "LED19") (pin "A") (pinfunction "A_A") (pintype "passive"))
      (node (ref "LED2") (pin "A") (pinfunction "A_A") (pintype "passive"))
      (node (ref "LED20") (pin "A") (pinfunction "A_A") (pintype "passive"))
      (node (ref "LED3") (pin "A") (pinfunction "A_A") (pintype "passive"))
      (node (ref "LED4") (pin "A") (pinfunction "A_A") (pintype "passive"))
      (node (ref "LED5") (pin "A") (pinfunction "A_A") (pintype "passive"))
      (node (ref "LED6") (pin "A") (pinfunction "A_A") (pintype "passive"))
      (node (ref "LED7") (pin "A") (pinfunction "A_A") (pintype "passive"))
      (node (ref "LED8") (pin "A") (pinfunction "A_A") (pintype "passive"))
      (node (ref "LED9") (pin "A") (pinfunction "A_A") (pintype "passive"))
      (node (ref "LS1") (pin "1") (pinfunction "1_1") (pintype "passive"))
      (node (ref "P1") (pin "2") (pinfunction "2_2") (pintype "passive"))
      (node (ref "P2") (pin "2") (pinfunction "2_2") (pintype "passive"))
      (node (ref "R1") (pin "2") (pinfunction "2_2") (pintype "passive"))
      (node (ref "R2") (pin "1") (pinfunction "1_1") (pintype "passive"))
      (node (ref "U1") (pin "17") (pinfunction "VCC_17") (pintype "passive"))
      (node (ref "U1") (pin "27") (pinfunction "AVCC_27") (pintype "passive"))
      (node (ref "U1") (pin "38") (pinfunction "VCC_38") (pintype "passive"))
      (node (ref "U1") (pin "5") (pinfunction "VCC_5") (pintype "passive"))
      (node (ref "U2") (pin "8") (pinfunction "VCC_8") (pintype "passive"))
      (node (ref "U3") (pin "9") (pinfunction "COM_9") (pintype "passive"))
      (node (ref "U4") (pin "9") (pinfunction "COM_9") (pintype "passive"))
      (node (ref "U5") (pin "9") (pinfunction "COM_9") (pintype "passive"))
    )
    (net (code "87") (name "unconnected-(P1-Pad3)") (class "Default")
      (node (ref "P1") (pin "3") (pinfunction "3_3") (pintype "passive"))
    )
    (net (code "88") (name "unconnected-(U1-PD3(INT1)-Pad12)") (class "Default")
      (node (ref "U1") (pin "12") (pinfunction "PD3(INT1)_12") (pintype "passive"))
    )
  )
)
